# RTC.net
KiCad netlist of a schematic drawn in Altium Designer
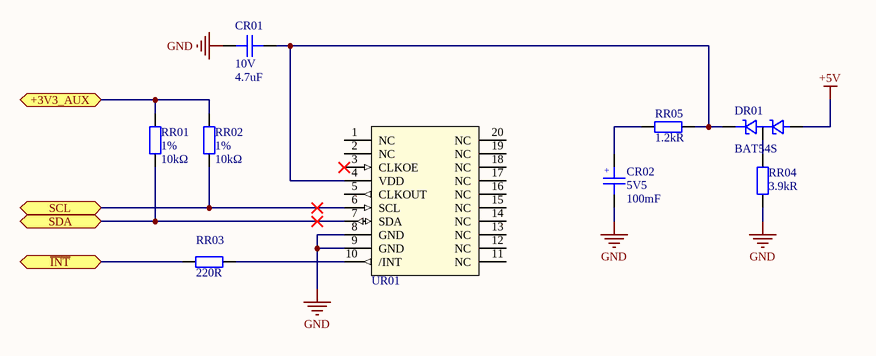
[diagram p0: RTC.SchDoc]

(export (version "E")
  (design (tool "Eeschema 10.0.6"))
  (components
    (comp (ref "CR01")
      (value "CAP CER 4.7UF 10V X5R 0603")
      (footprint "0603C")
      (description "4.7µF ±10% 10V Ceramic Capacitor X5R 0603 (1608 Metric)")
      (fields
        (field (name "MANUFACTURER") "Yageo")
        (field (name "MANUFACTURER PART NUMBER") "CC0603KRX5R6BB475")
        (field (name "VOLTAGE RATING") "10V")
        (field (name "CAPACITANCE") "4.7uF")
      )
      (libsource (lib "capacitors_smd") (part "CAP CER 4.7UF 10V X5R 0603"))
    )
    (comp (ref "CR02")
      (value "CAP ALUM 100 UF 20% 6.3 V SMD")
      (footprint "WCAP-ASLI_5x5.5")
      (description "100µF 6.3V Aluminum Electrolytic Capacitors Radial, Can - SMD  2000 Hrs @ 105°C")
      (fields
        (field (name "MANUFACTURER PART NUMBER") "865080142007")
        (field (name "MANUFACTURER") "Wurth Elektronik")
        (field (name "VOLTAGE RATING") "5V5")
        (field (name "CAPACITANCE") "100mF")
      )
      (libsource (lib "capacitors_alum_electr_poly") (part "CAP ALUM 100 UF 20% 6.3 V SMD"))
    )
    (comp (ref "DR01")
      (value "BAT54S")
      (description "Schottky DiodeS")
      (libsource (lib "diodes_schottky") (part "BAT54S"))
    )
    (comp (ref "RR01")
      (value "10 kOhms ±1% 0.1W, 1/10W Chip Resistor 0603 (1608 Metric)  Thick Film")
      (footprint "R0603")
      (fields
        (field (name "MANUFACTURER") "Yageo")
        (field (name "MANUFACTURER PART NUMBER") "RC0603FR-0710KL")
        (field (name "TOLERANCE") "1%")
        (field (name "RESISTANCE") "10kΩ")
      )
      (libsource (lib "resistors_smd") (part "RES SMD 10K OHM 1% 1/10W 0603"))
    )
    (comp (ref "RR02")
      (value "10 kOhms ±1% 0.1W, 1/10W Chip Resistor 0603 (1608 Metric)  Thick Film")
      (footprint "R0603")
      (fields
        (field (name "MANUFACTURER") "Yageo")
        (field (name "MANUFACTURER PART NUMBER") "RC0603FR-0710KL")
        (field (name "TOLERANCE") "1%")
        (field (name "RESISTANCE") "10kΩ")
      )
      (libsource (lib "resistors_smd") (part "RES SMD 10K OHM 1% 1/10W 0603"))
    )
    (comp (ref "RR03")
      (value "R 220Ω ±1% 0603 0.1W")
      (footprint "Resistor-0603")
      (description "Resistor")
      (fields
        (field (name "MANUFACTURER") "Stackpole Electronics")
        (field (name "MANUFACTURER PART NUMBER") "RMCF0603FT220R")
        (field (name "RESISTANCE") "220R")
      )
      (libsource (lib "resistors_smd") (part "R 220Ω ±1% 0603 0.1W"))
    )
    (comp (ref "RR04")
      (value "R 3kΩ ±1% 0603 0.1W")
      (footprint "Resistor-0603")
      (description "Resistor")
      (fields
        (field (name "MANUFACTURER") "Yageo")
        (field (name "MANUFACTURER PART NUMBER") "RC0603FR-073KL")
        (field (name "RESISTANCE") "3.9kR")
      )
      (libsource (lib "resistors_smd") (part "R 3kΩ ±1% 0603 0.1W"))
    )
    (comp (ref "RR05")
      (value "RES SMD 1.2K OHM 1% 1/16W 0402")
      (footprint "R0402")
      (description "1.2 kOhms ±1% 0.063W, 1/16W Chip Resistor 0402 (1005 Metric) Moisture Resistant Thick Film")
      (fields
        (field (name "MANUFACTURER") "Yageo")
        (field (name "MANUFACTURER PART NUMBER") "RC0402FR-071K2L")
        (field (name "RESISTANCE") "1.2kR")
      )
      (libsource (lib "resistors_smd") (part "RES SMD 1.2K OHM 1% 1/16W 0402"))
    )
    (comp (ref "UR01")
      (value "IC RTC-8564JE RTC CLK/CALENDAR I2C 20-VSOJ")
      (libsource (lib "EOB68200X") (part "IC RTC-8564JE RTC CLK/CALENDAR I2C 20-VSOJ"))
    )
  )
  (nets
    (net (code "1") (name "+5V") (class "Default")
      (node (ref "DR01") (pin "1") (pinfunction "1_1") (pintype "passive"))
    )
    (net (code "2") (name "/+3V3_AUX") (class "Default")
      (node (ref "RR01") (pin "2") (pinfunction "2_2") (pintype "passive"))
      (node (ref "RR02") (pin "2") (pinfunction "2_2") (pintype "passive"))
    )
    (net (code "3") (name "/INT") (class "Default")
      (node (ref "RR03") (pin "1") (pinfunction "1_1") (pintype "passive"))
    )
    (net (code "4") (name "/SCL") (class "Default")
      (node (ref "RR02") (pin "1") (pinfunction "1_1") (pintype "passive"))
      (node (ref "UR01") (pin "6") (pinfunction "SCL_6") (pintype "input"))
    )
    (net (code "5") (name "/SDA") (class "Default")
      (node (ref "RR01") (pin "1") (pinfunction "1_1") (pintype "passive"))
      (node (ref "UR01") (pin "7") (pinfunction "SDA_7") (pintype "bidirectional"))
    )
    (net (code "6") (name "GND") (class "Default")
      (node (ref "CR01") (pin "2") (pinfunction "2_2") (pintype "passive"))
      (node (ref "CR02") (pin "2") (pinfunction "2_2") (pintype "passive"))
      (node (ref "RR04") (pin "2") (pinfunction "2_2") (pintype "passive"))
      (node (ref "UR01") (pin "8") (pinfunction "GND_8") (pintype "power_in"))
      (node (ref "UR01") (pin "9") (pinfunction "GND_9") (pintype "power_in"))
    )
    (net (code "7") (name "Net-(CR02-Pad1)") (class "Default")
      (node (ref "CR02") (pin "1") (pinfunction "1_1") (pintype "passive"))
      (node (ref "RR05") (pin "2") (pinfunction "2_2") (pintype "passive"))
    )
    (net (code "8") (name "Net-(DR01-Pad3)") (class "Default")
      (node (ref "DR01") (pin "3") (pinfunction "3_3") (pintype "passive"))
      (node (ref "RR04") (pin "1") (pinfunction "1_1") (pintype "passive"))
    )
    (net (code "9") (name "Net-(UR01-VDD)") (class "Default")
      (node (ref "CR01") (pin "1") (pinfunction "1_1") (pintype "passive"))
      (node (ref "DR01") (pin "2") (pinfunction "2_2") (pintype "passive"))
      (node (ref "RR05") (pin "1") (pinfunction "1_1") (pintype "passive"))
      (node (ref "UR01") (pin "4") (pinfunction "VDD_4") (pintype "power_in"))
    )
    (net (code "10") (name "Net-(UR01-{slash}INT)") (class "Default")
      (node (ref "RR03") (pin "2") (pinfunction "2_2") (pintype "passive"))
      (node (ref "UR01") (pin "10") (pinfunction "/INT_10") (pintype "output"))
    )
    (net (code "11") (name "unconnected-(UR01-CLKOE-Pad3)") (class "Default")
      (node (ref "UR01") (pin "3") (pinfunction "CLKOE_3") (pintype "input+no_connect"))
    )
    (net (code "12") (name "unconnected-(UR01-CLKOUT-Pad5)") (class "Default")
      (node (ref "UR01") (pin "5") (pinfunction "CLKOUT_5") (pintype "output"))
    )
    (net (code "13") (name "unconnected-(UR01-NC-Pad1)") (class "Default")
      (node (ref "UR01") (pin "1") (pinfunction "NC_1") (pintype "passive"))
    )
    (net (code "14") (name "unconnected-(UR01-NC-Pad2)") (class "Default")
      (node (ref "UR01") (pin "2") (pinfunction "NC_2") (pintype "passive"))
    )
    (net (code "15") (name "unconnected-(UR01-NC-Pad11)") (class "Default")
      (node (ref "UR01") (pin "11") (pinfunction "NC_11") (pintype "passive"))
    )
    (net (code "16") (name "unconnected-(UR01-NC-Pad12)") (class "Default")
      (node (ref "UR01") (pin "12") (pinfunction "NC_12") (pintype "passive"))
    )
    (net (code "17") (name "unconnected-(UR01-NC-Pad13)") (class "Default")
      (node (ref "UR01") (pin "13") (pinfunction "NC_13") (pintype "passive"))
    )
    (net (code "18") (name "unconnected-(UR01-NC-Pad14)") (class "Default")
      (node (ref "UR01") (pin "14") (pinfunction "NC_14") (pintype "passive"))
    )
    (net (code "19") (name "unconnected-(UR01-NC-Pad15)") (class "Default")
      (node (ref "UR01") (pin "15") (pinfunction "NC_15") (pintype "passive"))
    )
    (net (code "20") (name "unconnected-(UR01-NC-Pad16)") (class "Default")
      (node (ref "UR01") (pin "16") (pinfunction "NC_16") (pintype "passive"))
    )
    (net (code "21") (name "unconnected-(UR01-NC-Pad17)") (class "Default")
      (node (ref "UR01") (pin "17") (pinfunction "NC_17") (pintype "passive"))
    )
    (net (code "22") (name "unconnected-(UR01-NC-Pad18)") (class "Default")
      (node (ref "UR01") (pin "18") (pinfunction "NC_18") (pintype "passive"))
    )
    (net (code "23") (name "unconnected-(UR01-NC-Pad19)") (class "Default")
      (node (ref "UR01") (pin "19") (pinfunction "NC_19") (pintype "passive"))
    )
    (net (code "24") (name "unconnected-(UR01-NC-Pad20)") (class "Default")
      (node (ref "UR01") (pin "20") (pinfunction "NC_20") (pintype "passive"))
    )
  )
)
